# johnson_counter.net
KiCad netlist of a schematic drawn in EAGLE
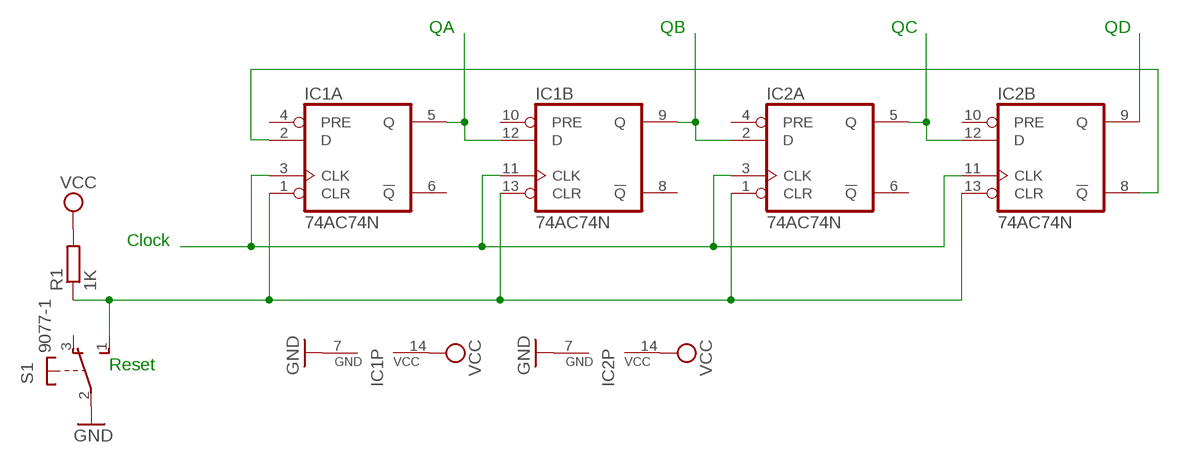
[diagram p0: schematic, sheet 1]

(export (version "E")
  (design (tool "Eeschema 10.0.6"))
  (components
    (comp (ref "IC1")
      (value "74AC74N")
      (footprint "eagle-import:DIL14")
      (libsource (lib "eagle-import") (part "7474NAC"))
    )
    (comp (ref "IC2")
      (value "74AC74N")
      (footprint "eagle-import:DIL14")
      (libsource (lib "eagle-import") (part "7474NAC"))
    )
    (comp (ref "R1")
      (value "1K")
      (footprint "eagle-import:0204_7")
      (libsource (lib "eagle-import") (part "R-EU_0204/7"))
    )
    (comp (ref "S1")
      (value "9077-1")
      (footprint "eagle-import:9077-1")
      (libsource (lib "eagle-import") (part "9077-1"))
    )
  )
  (nets
    (net (code "1") (name "GND") (class "Default")
      (node (ref "IC1") (pin "7") (pinfunction "GND_7") (pintype "power_in"))
      (node (ref "IC2") (pin "7") (pinfunction "GND_7") (pintype "power_in"))
      (node (ref "S1") (pin "2") (pinfunction "P_2") (pintype "passive"))
    )
    (net (code "2") (name "Net-(IC1A-CLK)") (class "Default")
      (node (ref "IC1") (pin "11") (pinfunction "CLK_11") (pintype "input"))
      (node (ref "IC1") (pin "3") (pinfunction "CLK_3") (pintype "input"))
      (node (ref "IC2") (pin "11") (pinfunction "CLK_11") (pintype "input"))
      (node (ref "IC2") (pin "3") (pinfunction "CLK_3") (pintype "input"))
    )
    (net (code "3") (name "Net-(IC1A-CLR)") (class "Default")
      (node (ref "IC1") (pin "1") (pinfunction "CLR_1") (pintype "input"))
      (node (ref "IC1") (pin "13") (pinfunction "CLR_13") (pintype "input"))
      (node (ref "IC2") (pin "1") (pinfunction "CLR_1") (pintype "input"))
      (node (ref "IC2") (pin "13") (pinfunction "CLR_13") (pintype "input"))
      (node (ref "R1") (pin "1") (pinfunction "1_1") (pintype "passive"))
      (node (ref "S1") (pin "1") (pinfunction "S_1") (pintype "passive"))
    )
    (net (code "4") (name "Net-(IC1A-D)") (class "Default")
      (node (ref "IC1") (pin "2") (pinfunction "D_2") (pintype "input"))
      (node (ref "IC2") (pin "8") (pinfunction "~{Q}_8") (pintype "output"))
    )
    (net (code "5") (name "Net-(IC1A-Q)") (class "Default")
      (node (ref "IC1") (pin "12") (pinfunction "D_12") (pintype "input"))
      (node (ref "IC1") (pin "5") (pinfunction "Q_5") (pintype "output"))
    )
    (net (code "6") (name "Net-(IC1B-Q)") (class "Default")
      (node (ref "IC1") (pin "9") (pinfunction "Q_9") (pintype "output"))
      (node (ref "IC2") (pin "2") (pinfunction "D_2") (pintype "input"))
    )
    (net (code "7") (name "Net-(IC2A-Q)") (class "Default")
      (node (ref "IC2") (pin "12") (pinfunction "D_12") (pintype "input"))
      (node (ref "IC2") (pin "5") (pinfunction "Q_5") (pintype "output"))
    )
    (net (code "8") (name "VCC") (class "Default")
      (node (ref "IC1") (pin "14") (pinfunction "VCC_14") (pintype "power_in"))
      (node (ref "IC2") (pin "14") (pinfunction "VCC_14") (pintype "power_in"))
      (node (ref "R1") (pin "2") (pinfunction "2_2") (pintype "passive"))
    )
    (net (code "9") (name "unconnected-(IC1A-PRE-Pad4)") (class "Default")
      (node (ref "IC1") (pin "4") (pinfunction "PRE_4") (pintype "input"))
    )
    (net (code "10") (name "unconnected-(IC1A-~{Q}-Pad6)") (class "Default")
      (node (ref "IC1") (pin "6") (pinfunction "~{Q}_6") (pintype "output"))
    )
    (net (code "11") (name "unconnected-(IC1B-PRE-Pad10)") (class "Default")
      (node (ref "IC1") (pin "10") (pinfunction "PRE_10") (pintype "input"))
    )
    (net (code "12") (name "unconnected-(IC1B-~{Q}-Pad8)") (class "Default")
      (node (ref "IC1") (pin "8") (pinfunction "~{Q}_8") (pintype "output"))
    )
    (net (code "13") (name "unconnected-(IC2A-PRE-Pad4)") (class "Default")
      (node (ref "IC2") (pin "4") (pinfunction "PRE_4") (pintype "input"))
    )
    (net (code "14") (name "unconnected-(IC2A-~{Q}-Pad6)") (class "Default")
      (node (ref "IC2") (pin "6") (pinfunction "~{Q}_6") (pintype "output"))
    )
    (net (code "15") (name "unconnected-(IC2B-PRE-Pad10)") (class "Default")
      (node (ref "IC2") (pin "10") (pinfunction "PRE_10") (pintype "input"))
    )
    (net (code "16") (name "unconnected-(IC2B-Q-Pad9)") (class "Default")
      (node (ref "IC2") (pin "9") (pinfunction "Q_9") (pintype "output"))
    )
    (net (code "17") (name "unconnected-(S1-O-Pad3)") (class "Default")
      (node (ref "S1") (pin "3") (pinfunction "O_3") (pintype "passive"))
    )
  )
)
